# goodfet42.net
KiCad netlist of a schematic drawn in EAGLE
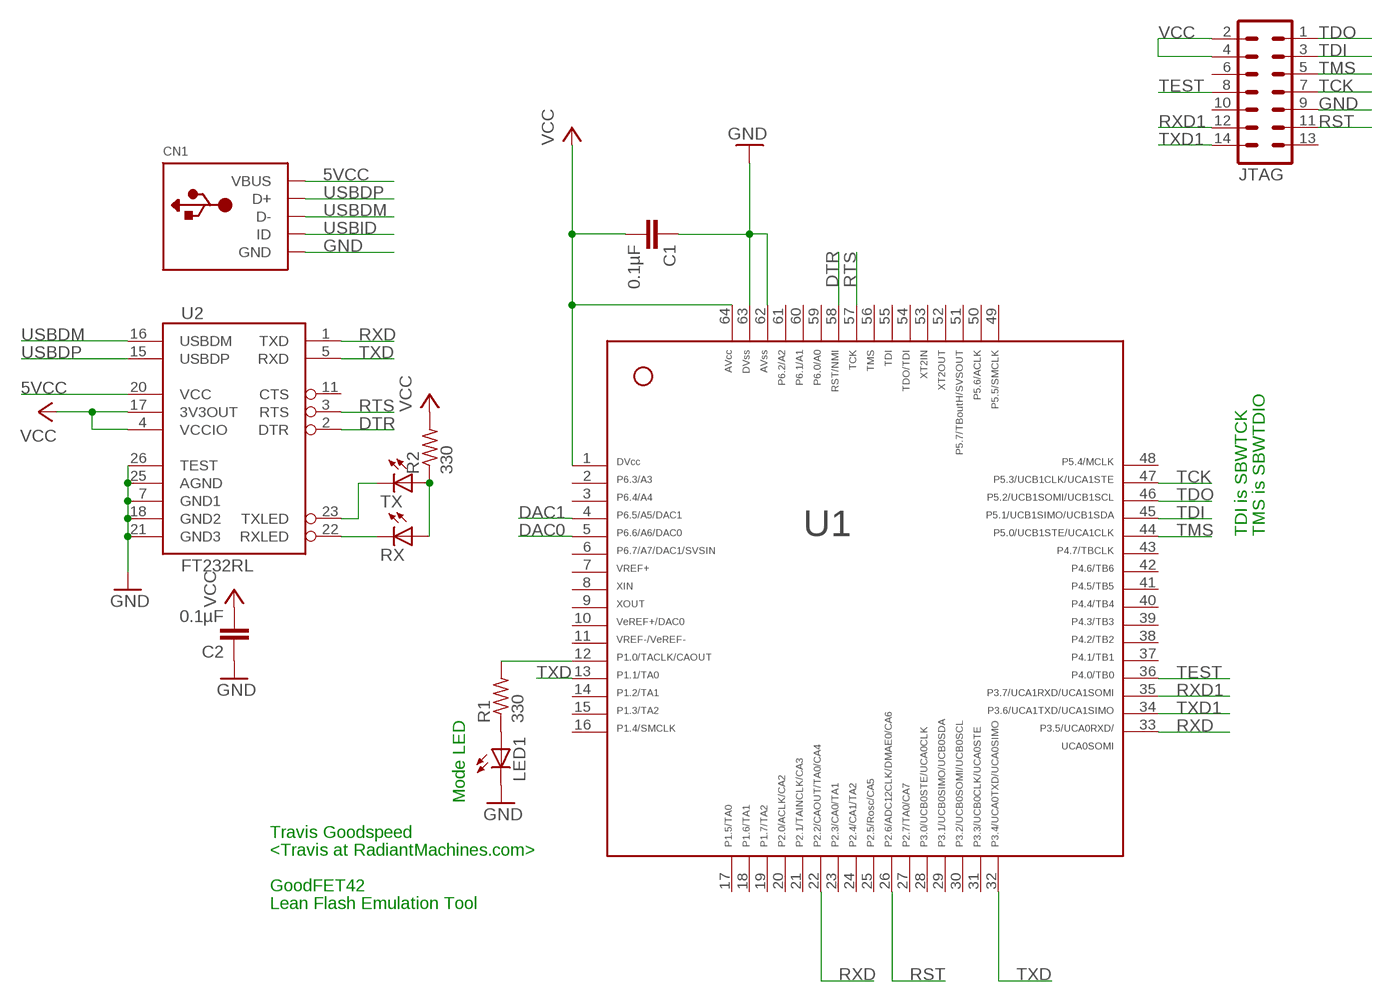
[diagram p0: schematic, sheet 1]

(export (version "E")
  (design (tool "Eeschema 10.0.6"))
  (components
    (comp (ref "C1")
      (value "0.1µF")
      (footprint "eagle-import:C0603")
      (libsource (lib "eagle-import") (part "C-EUC0603"))
    )
    (comp (ref "C2")
      (value "0.1µF")
      (footprint "eagle-import:C0603")
      (libsource (lib "eagle-import") (part "C-EUC0603"))
    )
    (comp (ref "CN1")
      (value "USBMINIB")
      (footprint "eagle-import:USB-MINIB")
      (libsource (lib "eagle-import") (part "USBMINIB"))
    )
    (comp (ref "JTAG")
      (value "MA07-2")
      (footprint "eagle-import:MA07-2")
      (libsource (lib "eagle-import") (part "MA07-2"))
    )
    (comp (ref "LED1")
      (value "LEDCHIP-LED0603")
      (footprint "eagle-import:CHIP-LED0603")
      (libsource (lib "eagle-import") (part "LEDCHIP-LED0603"))
    )
    (comp (ref "R1")
      (value "330")
      (footprint "eagle-import:R0603")
      (libsource (lib "eagle-import") (part "R-US_R0603"))
    )
    (comp (ref "R2")
      (value "330")
      (footprint "eagle-import:R0603")
      (libsource (lib "eagle-import") (part "R-US_R0603"))
    )
    (comp (ref "RX")
      (value "LEDCHIP-LED0603")
      (footprint "eagle-import:CHIP-LED0603")
      (libsource (lib "eagle-import") (part "LEDCHIP-LED0603"))
    )
    (comp (ref "TX")
      (value "LEDCHIP-LED0603")
      (footprint "eagle-import:CHIP-LED0603")
      (libsource (lib "eagle-import") (part "LEDCHIP-LED0603"))
    )
    (comp (ref "U1")
      (value "MSP430F2618TPM")
      (footprint "eagle-import:PM_PAG64")
      (libsource (lib "eagle-import") (part "F261X---PM64"))
    )
    (comp (ref "U2")
      (value "FT232RL")
      (footprint "eagle-import:SSOP28DB")
      (libsource (lib "eagle-import") (part "FT232RL-BASICSSOP"))
    )
  )
  (nets
    (net (code "1") (name "/5VCC") (class "Default")
      (node (ref "CN1") (pin "VBUS") (pinfunction "VBUS_VBUS") (pintype "power_in"))
      (node (ref "U2") (pin "20") (pinfunction "VCC_20") (pintype "power_in"))
    )
    (net (code "2") (name "/DAC0") (class "Default")
      (node (ref "U1") (pin "5") (pinfunction "5_5") (pintype "bidirectional"))
    )
    (net (code "3") (name "/DAC1") (class "Default")
      (node (ref "U1") (pin "4") (pinfunction "4_4") (pintype "bidirectional"))
    )
    (net (code "4") (name "/DTR") (class "Default")
      (node (ref "U1") (pin "58") (pinfunction "58_58") (pintype "input"))
      (node (ref "U2") (pin "2") (pinfunction "DTR_2") (pintype "bidirectional"))
    )
    (net (code "5") (name "/RST") (class "Default")
      (node (ref "JTAG") (pin "11") (pinfunction "11_11") (pintype "passive"))
      (node (ref "U1") (pin "26") (pinfunction "26_26") (pintype "bidirectional"))
    )
    (net (code "6") (name "/RTS") (class "Default")
      (node (ref "U1") (pin "57") (pinfunction "57_57") (pintype "input"))
      (node (ref "U2") (pin "3") (pinfunction "RTS_3") (pintype "bidirectional"))
    )
    (net (code "7") (name "/RXD") (class "Default")
      (node (ref "U1") (pin "22") (pinfunction "22_22") (pintype "bidirectional"))
      (node (ref "U1") (pin "33") (pinfunction "33_33") (pintype "bidirectional"))
      (node (ref "U2") (pin "1") (pinfunction "TXD_1") (pintype "output"))
    )
    (net (code "8") (name "/RXD1") (class "Default")
      (node (ref "JTAG") (pin "12") (pinfunction "12_12") (pintype "passive"))
      (node (ref "U1") (pin "35") (pinfunction "35_35") (pintype "bidirectional"))
    )
    (net (code "9") (name "/TCK") (class "Default")
      (node (ref "JTAG") (pin "7") (pinfunction "7_7") (pintype "passive"))
      (node (ref "U1") (pin "47") (pinfunction "47_47") (pintype "bidirectional"))
    )
    (net (code "10") (name "/TDI") (class "Default")
      (node (ref "JTAG") (pin "3") (pinfunction "3_3") (pintype "passive"))
      (node (ref "U1") (pin "45") (pinfunction "45_45") (pintype "bidirectional"))
    )
    (net (code "11") (name "/TDO") (class "Default")
      (node (ref "JTAG") (pin "1") (pinfunction "1_1") (pintype "passive"))
      (node (ref "U1") (pin "46") (pinfunction "46_46") (pintype "bidirectional"))
    )
    (net (code "12") (name "/TEST") (class "Default")
      (node (ref "JTAG") (pin "8") (pinfunction "8_8") (pintype "passive"))
      (node (ref "U1") (pin "36") (pinfunction "36_36") (pintype "output"))
    )
    (net (code "13") (name "/TMS") (class "Default")
      (node (ref "JTAG") (pin "5") (pinfunction "5_5") (pintype "passive"))
      (node (ref "U1") (pin "44") (pinfunction "44_44") (pintype "bidirectional"))
    )
    (net (code "14") (name "/TXD") (class "Default")
      (node (ref "U1") (pin "13") (pinfunction "13_13") (pintype "bidirectional"))
      (node (ref "U1") (pin "32") (pinfunction "32_32") (pintype "bidirectional"))
      (node (ref "U2") (pin "5") (pinfunction "RXD_5") (pintype "input"))
    )
    (net (code "15") (name "/TXD1") (class "Default")
      (node (ref "JTAG") (pin "14") (pinfunction "14_14") (pintype "passive"))
      (node (ref "U1") (pin "34") (pinfunction "34_34") (pintype "bidirectional"))
    )
    (net (code "16") (name "/USBDM") (class "Default")
      (node (ref "CN1") (pin "D-") (pinfunction "D-_D-") (pintype "bidirectional"))
      (node (ref "U2") (pin "16") (pinfunction "USBDM_16") (pintype "bidirectional"))
    )
    (net (code "17") (name "/USBDP") (class "Default")
      (node (ref "CN1") (pin "D+") (pinfunction "D+_D+") (pintype "bidirectional"))
      (node (ref "U2") (pin "15") (pinfunction "USBDP_15") (pintype "bidirectional"))
    )
    (net (code "18") (name "/USBID") (class "Default")
      (node (ref "CN1") (pin "ID") (pinfunction "ID_ID") (pintype "bidirectional"))
    )
    (net (code "19") (name "GND") (class "Default")
      (node (ref "C1") (pin "1") (pinfunction "1_1") (pintype "passive"))
      (node (ref "C2") (pin "1") (pinfunction "1_1") (pintype "passive"))
      (node (ref "CN1") (pin "GND") (pinfunction "GND_GND") (pintype "power_in"))
      (node (ref "JTAG") (pin "9") (pinfunction "9_9") (pintype "passive"))
      (node (ref "LED1") (pin "C") (pinfunction "C_C") (pintype "passive"))
      (node (ref "U1") (pin "62") (pinfunction "62_62") (pintype "power_in"))
      (node (ref "U1") (pin "63") (pinfunction "63_63") (pintype "power_in"))
      (node (ref "U2") (pin "18") (pinfunction "GND2_18") (pintype "power_in"))
      (node (ref "U2") (pin "21") (pinfunction "GND3_21") (pintype "power_in"))
      (node (ref "U2") (pin "25") (pinfunction "AGND_25") (pintype "power_in"))
      (node (ref "U2") (pin "26") (pinfunction "TEST_26") (pintype "input"))
      (node (ref "U2") (pin "7") (pinfunction "GND1_7") (pintype "power_in"))
    )
    (net (code "20") (name "Net-(LED1-PadA)") (class "Default")
      (node (ref "LED1") (pin "A") (pinfunction "A_A") (pintype "passive"))
      (node (ref "R1") (pin "1") (pinfunction "1_1") (pintype "passive"))
    )
    (net (code "21") (name "Net-(R1-Pad2)") (class "Default")
      (node (ref "R1") (pin "2") (pinfunction "2_2") (pintype "passive"))
      (node (ref "U1") (pin "12") (pinfunction "12_12") (pintype "bidirectional"))
    )
    (net (code "22") (name "Net-(R2-Pad1)") (class "Default")
      (node (ref "R2") (pin "1") (pinfunction "1_1") (pintype "passive"))
      (node (ref "RX") (pin "A") (pinfunction "A_A") (pintype "passive"))
      (node (ref "TX") (pin "A") (pinfunction "A_A") (pintype "passive"))
    )
    (net (code "23") (name "Net-(U2-RXLED)") (class "Default")
      (node (ref "RX") (pin "C") (pinfunction "C_C") (pintype "passive"))
      (node (ref "U2") (pin "22") (pinfunction "RXLED_22") (pintype "bidirectional"))
    )
    (net (code "24") (name "Net-(U2-TXLED)") (class "Default")
      (node (ref "TX") (pin "C") (pinfunction "C_C") (pintype "passive"))
      (node (ref "U2") (pin "23") (pinfunction "TXLED_23") (pintype "bidirectional"))
    )
    (net (code "25") (name "VCC") (class "Default")
      (node (ref "C1") (pin "2") (pinfunction "2_2") (pintype "passive"))
      (node (ref "C2") (pin "2") (pinfunction "2_2") (pintype "passive"))
      (node (ref "JTAG") (pin "2") (pinfunction "2_2") (pintype "passive"))
      (node (ref "JTAG") (pin "4") (pinfunction "4_4") (pintype "passive"))
      (node (ref "R2") (pin "2") (pinfunction "2_2") (pintype "passive"))
      (node (ref "U1") (pin "1") (pinfunction "1_1") (pintype "power_in"))
      (node (ref "U1") (pin "64") (pinfunction "64_64") (pintype "power_in"))
      (node (ref "U2") (pin "17") (pinfunction "3V3OUT_17") (pintype "output"))
      (node (ref "U2") (pin "4") (pinfunction "VCCIO_4") (pintype "power_in"))
    )
    (net (code "26") (name "unconnected-(JTAG-Pad6)") (class "Default")
      (node (ref "JTAG") (pin "6") (pinfunction "6_6") (pintype "passive"))
    )
    (net (code "27") (name "unconnected-(JTAG-Pad10)") (class "Default")
      (node (ref "JTAG") (pin "10") (pinfunction "10_10") (pintype "passive"))
    )
    (net (code "28") (name "unconnected-(JTAG-Pad13)") (class "Default")
      (node (ref "JTAG") (pin "13") (pinfunction "13_13") (pintype "passive"))
    )
    (net (code "29") (name "unconnected-(U1-Pad2)") (class "Default")
      (node (ref "U1") (pin "2") (pinfunction "2_2") (pintype "bidirectional"))
    )
    (net (code "30") (name "unconnected-(U1-Pad3)") (class "Default")
      (node (ref "U1") (pin "3") (pinfunction "3_3") (pintype "bidirectional"))
    )
    (net (code "31") (name "unconnected-(U1-Pad6)") (class "Default")
      (node (ref "U1") (pin "6") (pinfunction "6_6") (pintype "bidirectional"))
    )
    (net (code "32") (name "unconnected-(U1-Pad7)") (class "Default")
      (node (ref "U1") (pin "7") (pinfunction "7_7") (pintype "output"))
    )
    (net (code "33") (name "unconnected-(U1-Pad8)") (class "Default")
      (node (ref "U1") (pin "8") (pinfunction "8_8") (pintype "input"))
    )
    (net (code "34") (name "unconnected-(U1-Pad9)") (class "Default")
      (node (ref "U1") (pin "9") (pinfunction "9_9") (pintype "output"))
    )
    (net (code "35") (name "unconnected-(U1-Pad10)") (class "Default")
      (node (ref "U1") (pin "10") (pinfunction "10_10") (pintype "bidirectional"))
    )
    (net (code "36") (name "unconnected-(U1-Pad11)") (class "Default")
      (node (ref "U1") (pin "11") (pinfunction "11_11") (pintype "bidirectional"))
    )
    (net (code "37") (name "unconnected-(U1-Pad14)") (class "Default")
      (node (ref "U1") (pin "14") (pinfunction "14_14") (pintype "bidirectional"))
    )
    (net (code "38") (name "unconnected-(U1-Pad15)") (class "Default")
      (node (ref "U1") (pin "15") (pinfunction "15_15") (pintype "bidirectional"))
    )
    (net (code "39") (name "unconnected-(U1-Pad16)") (class "Default")
      (node (ref "U1") (pin "16") (pinfunction "16_16") (pintype "bidirectional"))
    )
    (net (code "40") (name "unconnected-(U1-Pad17)") (class "Default")
      (node (ref "U1") (pin "17") (pinfunction "17_17") (pintype "bidirectional"))
    )
    (net (code "41") (name "unconnected-(U1-Pad18)") (class "Default")
      (node (ref "U1") (pin "18") (pinfunction "18_18") (pintype "bidirectional"))
    )
    (net (code "42") (name "unconnected-(U1-Pad19)") (class "Default")
      (node (ref "U1") (pin "19") (pinfunction "19_19") (pintype "bidirectional"))
    )
    (net (code "43") (name "unconnected-(U1-Pad20)") (class "Default")
      (node (ref "U1") (pin "20") (pinfunction "20_20") (pintype "bidirectional"))
    )
    (net (code "44") (name "unconnected-(U1-Pad21)") (class "Default")
      (node (ref "U1") (pin "21") (pinfunction "21_21") (pintype "bidirectional"))
    )
    (net (code "45") (name "unconnected-(U1-Pad23)") (class "Default")
      (node (ref "U1") (pin "23") (pinfunction "23_23") (pintype "bidirectional"))
    )
    (net (code "46") (name "unconnected-(U1-Pad24)") (class "Default")
      (node (ref "U1") (pin "24") (pinfunction "24_24") (pintype "bidirectional"))
    )
    (net (code "47") (name "unconnected-(U1-Pad25)") (class "Default")
      (node (ref "U1") (pin "25") (pinfunction "25_25") (pintype "bidirectional"))
    )
    (net (code "48") (name "unconnected-(U1-Pad27)") (class "Default")
      (node (ref "U1") (pin "27") (pinfunction "27_27") (pintype "bidirectional"))
    )
    (net (code "49") (name "unconnected-(U1-Pad28)") (class "Default")
      (node (ref "U1") (pin "28") (pinfunction "28_28") (pintype "bidirectional"))
    )
    (net (code "50") (name "unconnected-(U1-Pad29)") (class "Default")
      (node (ref "U1") (pin "29") (pinfunction "29_29") (pintype "bidirectional"))
    )
    (net (code "51") (name "unconnected-(U1-Pad30)") (class "Default")
      (node (ref "U1") (pin "30") (pinfunction "30_30") (pintype "bidirectional"))
    )
    (net (code "52") (name "unconnected-(U1-Pad31)") (class "Default")
      (node (ref "U1") (pin "31") (pinfunction "31_31") (pintype "bidirectional"))
    )
    (net (code "53") (name "unconnected-(U1-Pad37)") (class "Default")
      (node (ref "U1") (pin "37") (pinfunction "37_37") (pintype "bidirectional"))
    )
    (net (code "54") (name "unconnected-(U1-Pad38)") (class "Default")
      (node (ref "U1") (pin "38") (pinfunction "38_38") (pintype "bidirectional"))
    )
    (net (code "55") (name "unconnected-(U1-Pad39)") (class "Default")
      (node (ref "U1") (pin "39") (pinfunction "39_39") (pintype "bidirectional"))
    )
    (net (code "56") (name "unconnected-(U1-Pad40)") (class "Default")
      (node (ref "U1") (pin "40") (pinfunction "40_40") (pintype "input"))
    )
    (net (code "57") (name "unconnected-(U1-Pad41)") (class "Default")
      (node (ref "U1") (pin "41") (pinfunction "41_41") (pintype "bidirectional"))
    )
    (net (code "58") (name "unconnected-(U1-Pad42)") (class "Default")
      (node (ref "U1") (pin "42") (pinfunction "42_42") (pintype "bidirectional"))
    )
    (net (code "59") (name "unconnected-(U1-Pad43)") (class "Default")
      (node (ref "U1") (pin "43") (pinfunction "43_43") (pintype "bidirectional"))
    )
    (net (code "60") (name "unconnected-(U1-Pad48)") (class "Default")
      (node (ref "U1") (pin "48") (pinfunction "48_48") (pintype "bidirectional"))
    )
    (net (code "61") (name "unconnected-(U1-Pad49)") (class "Default")
      (node (ref "U1") (pin "49") (pinfunction "49_49") (pintype "bidirectional"))
    )
    (net (code "62") (name "unconnected-(U1-Pad50)") (class "Default")
      (node (ref "U1") (pin "50") (pinfunction "50_50") (pintype "bidirectional"))
    )
    (net (code "63") (name "unconnected-(U1-Pad51)") (class "Default")
      (node (ref "U1") (pin "51") (pinfunction "51_51") (pintype "bidirectional"))
    )
    (net (code "64") (name "unconnected-(U1-Pad52)") (class "Default")
      (node (ref "U1") (pin "52") (pinfunction "52_52") (pintype "output"))
    )
    (net (code "65") (name "unconnected-(U1-Pad53)") (class "Default")
      (node (ref "U1") (pin "53") (pinfunction "53_53") (pintype "input"))
    )
    (net (code "66") (name "unconnected-(U1-Pad54)") (class "Default")
      (node (ref "U1") (pin "54") (pinfunction "54_54") (pintype "bidirectional"))
    )
    (net (code "67") (name "unconnected-(U1-Pad55)") (class "Default")
      (node (ref "U1") (pin "55") (pinfunction "55_55") (pintype "input"))
    )
    (net (code "68") (name "unconnected-(U1-Pad56)") (class "Default")
      (node (ref "U1") (pin "56") (pinfunction "56_56") (pintype "input"))
    )
    (net (code "69") (name "unconnected-(U1-Pad59)") (class "Default")
      (node (ref "U1") (pin "59") (pinfunction "59_59") (pintype "bidirectional"))
    )
    (net (code "70") (name "unconnected-(U1-Pad60)") (class "Default")
      (node (ref "U1") (pin "60") (pinfunction "60_60") (pintype "bidirectional"))
    )
    (net (code "71") (name "unconnected-(U1-Pad61)") (class "Default")
      (node (ref "U1") (pin "61") (pinfunction "61_61") (pintype "bidirectional"))
    )
    (net (code "72") (name "unconnected-(U2-CTS-Pad11)") (class "Default")
      (node (ref "U2") (pin "11") (pinfunction "CTS_11") (pintype "bidirectional"))
    )
  )
)
